# Stepper_Motor_Driver.net
KiCad netlist of a schematic drawn in Altium Designer
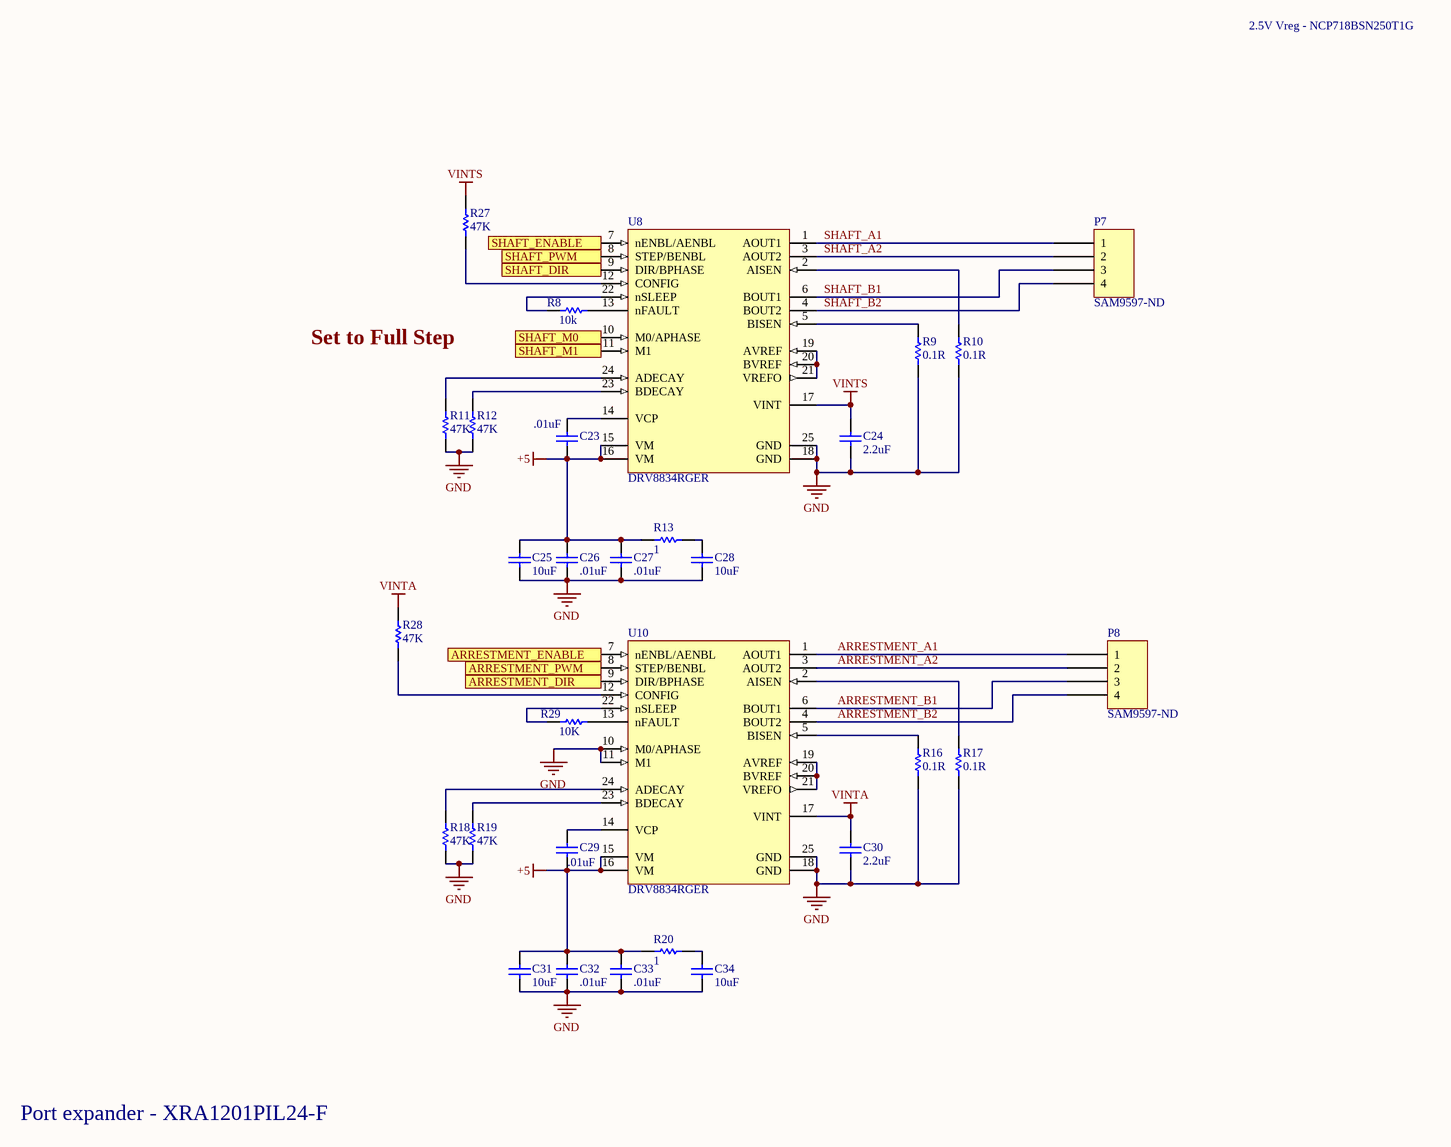
[diagram p0: Stepper Motor Driver.SchDoc]

(export (version "E")
  (design (tool "Eeschema 10.0.6"))
  (components
    (comp (ref "C23")
      (value ".01uF")
      (footprint "CAPC0402(1005)60_N")
      (description "CAP 220pF 25V ±10% 0402 (1005 Metric) Thickness 0.6mm SMD")
      (libsource (lib "Altium Content Vault") (part "CMP-1034-01365-1"))
    )
    (comp (ref "C24")
      (value "2.2uF")
      (footprint "CAPC0402(1005)60_N")
      (description "CAP 220pF 25V ±10% 0402 (1005 Metric) Thickness 0.6mm SMD")
      (libsource (lib "Altium Content Vault") (part "CMP-1034-01365-1"))
    )
    (comp (ref "C25")
      (value "10uF")
      (footprint "CAPC0402(1005)60_N")
      (description "CAP 220pF 25V ±10% 0402 (1005 Metric) Thickness 0.6mm SMD")
      (libsource (lib "Altium Content Vault") (part "CMP-1034-01365-1"))
    )
    (comp (ref "C26")
      (value ".01uF")
      (footprint "CAPC0402(1005)60_N")
      (description "CAP 220pF 25V ±10% 0402 (1005 Metric) Thickness 0.6mm SMD")
      (libsource (lib "Altium Content Vault") (part "CMP-1034-01365-1"))
    )
    (comp (ref "C27")
      (value ".01uF")
      (footprint "CAPC0402(1005)60_N")
      (description "CAP 220pF 25V ±10% 0402 (1005 Metric) Thickness 0.6mm SMD")
      (libsource (lib "Altium Content Vault") (part "CMP-1034-01365-1"))
    )
    (comp (ref "C28")
      (value "10uF")
      (footprint "CAPC0402(1005)60_N")
      (description "CAP 220pF 25V ±10% 0402 (1005 Metric) Thickness 0.6mm SMD")
      (libsource (lib "Altium Content Vault") (part "CMP-1034-01365-1"))
    )
    (comp (ref "C29")
      (value ".01uF")
      (footprint "CAPC0402(1005)60_N")
      (description "CAP 220pF 25V ±10% 0402 (1005 Metric) Thickness 0.6mm SMD")
      (libsource (lib "Altium Content Vault") (part "CMP-1034-01365-1"))
    )
    (comp (ref "C30")
      (value "2.2uF")
      (footprint "CAPC0402(1005)60_N")
      (description "CAP 220pF 25V ±10% 0402 (1005 Metric) Thickness 0.6mm SMD")
      (libsource (lib "Altium Content Vault") (part "CMP-1034-01365-1"))
    )
    (comp (ref "C31")
      (value "10uF")
      (footprint "CAPC0402(1005)60_N")
      (description "CAP 220pF 25V ±10% 0402 (1005 Metric) Thickness 0.6mm SMD")
      (libsource (lib "Altium Content Vault") (part "CMP-1034-01365-1"))
    )
    (comp (ref "C32")
      (value ".01uF")
      (footprint "CAPC0402(1005)60_N")
      (description "CAP 220pF 25V ±10% 0402 (1005 Metric) Thickness 0.6mm SMD")
      (libsource (lib "Altium Content Vault") (part "CMP-1034-01365-1"))
    )
    (comp (ref "C33")
      (value ".01uF")
      (footprint "CAPC0402(1005)60_N")
      (description "CAP 220pF 25V ±10% 0402 (1005 Metric) Thickness 0.6mm SMD")
      (libsource (lib "Altium Content Vault") (part "CMP-1034-01365-1"))
    )
    (comp (ref "C34")
      (value "10uF")
      (footprint "CAPC0402(1005)60_N")
      (description "CAP 220pF 25V ±10% 0402 (1005 Metric) Thickness 0.6mm SMD")
      (libsource (lib "Altium Content Vault") (part "CMP-1034-01365-1"))
    )
    (comp (ref "P7")
      (value "IPL1-104-01-L-S-RA-K")
      (footprint "IPL1-104-01-L-S-RA-K")
      (fields (field (name "SUPPLIER PART NUMBER 1") "SAM9597-ND"))
      (libsource (lib "ZLS_Schematic_lib") (part "IPL1-104-01-L-S-RA-K"))
    )
    (comp (ref "P8")
      (value "IPL1-104-01-L-S-RA-K")
      (footprint "IPL1-104-01-L-S-RA-K")
      (fields (field (name "SUPPLIER PART NUMBER 1") "SAM9597-ND"))
      (libsource (lib "ZLS_Schematic_lib") (part "IPL1-104-01-L-S-RA-K"))
    )
    (comp (ref "R8")
      (value "10k")
      (footprint "RESC0402(1005)_M")
      (libsource (lib "Altium Content Vault") (part "CMP-1011-00463-1"))
    )
    (comp (ref "R9")
      (value "0.1R")
      (footprint "RESC0402(1005)_M")
      (libsource (lib "Altium Content Vault") (part "CMP-1011-00463-1"))
    )
    (comp (ref "R10")
      (value "0.1R")
      (footprint "RESC0402(1005)_M")
      (libsource (lib "Altium Content Vault") (part "CMP-1011-00463-1"))
    )
    (comp (ref "R11")
      (value "47K")
      (footprint "RESC0402(1005)_M")
      (libsource (lib "Altium Content Vault") (part "CMP-1011-00463-1"))
    )
    (comp (ref "R12")
      (value "47K")
      (footprint "RESC0402(1005)_M")
      (libsource (lib "Altium Content Vault") (part "CMP-1011-00463-1"))
    )
    (comp (ref "R13")
      (value "1")
      (footprint "RESC0402(1005)_M")
      (libsource (lib "Altium Content Vault") (part "CMP-1011-00463-1"))
    )
    (comp (ref "R16")
      (value "0.1R")
      (footprint "RESC0402(1005)_M")
      (libsource (lib "Altium Content Vault") (part "CMP-1011-00463-1"))
    )
    (comp (ref "R17")
      (value "0.1R")
      (footprint "RESC0402(1005)_M")
      (libsource (lib "Altium Content Vault") (part "CMP-1011-00463-1"))
    )
    (comp (ref "R18")
      (value "47K")
      (footprint "RESC0402(1005)_M")
      (libsource (lib "Altium Content Vault") (part "CMP-1011-00463-1"))
    )
    (comp (ref "R19")
      (value "47K")
      (footprint "RESC0402(1005)_M")
      (libsource (lib "Altium Content Vault") (part "CMP-1011-00463-1"))
    )
    (comp (ref "R20")
      (value "1")
      (footprint "RESC0402(1005)_M")
      (libsource (lib "Altium Content Vault") (part "CMP-1011-00463-1"))
    )
    (comp (ref "R27")
      (value "47K")
      (footprint "RESC0402(1005)_M")
      (libsource (lib "Altium Content Vault") (part "CMP-1011-00463-1"))
    )
    (comp (ref "R28")
      (value "47K")
      (footprint "RESC0402(1005)_M")
      (libsource (lib "Altium Content Vault") (part "CMP-1011-00463-1"))
    )
    (comp (ref "R29")
      (value "10K")
      (footprint "RESC0402(1005)_M")
      (libsource (lib "Altium Content Vault") (part "CMP-1011-00463-1"))
    )
    (comp (ref "U8")
      (value "DRV8834RGER")
      (footprint "RGE0024B_V")
      (libsource (lib "Altium Content Vault") (part "TI-DRV8834RGE-24"))
    )
    (comp (ref "U10")
      (value "DRV8834RGER")
      (footprint "RGE0024B_V")
      (libsource (lib "Altium Content Vault") (part "TI-DRV8834RGE-24"))
    )
  )
  (nets
    (net (code "1") (name "+5") (class "Default")
      (node (ref "C23") (pin "1") (pinfunction "1_1") (pintype "passive"))
      (node (ref "C25") (pin "2") (pinfunction "2_2") (pintype "passive"))
      (node (ref "C26") (pin "2") (pinfunction "2_2") (pintype "passive"))
      (node (ref "C27") (pin "2") (pinfunction "2_2") (pintype "passive"))
      (node (ref "C29") (pin "1") (pinfunction "1_1") (pintype "passive"))
      (node (ref "C31") (pin "2") (pinfunction "2_2") (pintype "passive"))
      (node (ref "C32") (pin "2") (pinfunction "2_2") (pintype "passive"))
      (node (ref "C33") (pin "2") (pinfunction "2_2") (pintype "passive"))
      (node (ref "R13") (pin "1") (pinfunction "1_1") (pintype "passive"))
      (node (ref "R20") (pin "1") (pinfunction "1_1") (pintype "passive"))
      (node (ref "U10") (pin "15") (pinfunction "VM_15") (pintype "power_in"))
      (node (ref "U10") (pin "16") (pinfunction "VM_16") (pintype "power_in"))
      (node (ref "U8") (pin "15") (pinfunction "VM_15") (pintype "power_in"))
      (node (ref "U8") (pin "16") (pinfunction "VM_16") (pintype "power_in"))
    )
    (net (code "2") (name "/ARRESTMENT_A1") (class "Default")
      (node (ref "P8") (pin "1") (pinfunction "1_1") (pintype "passive"))
      (node (ref "U10") (pin "1") (pinfunction "AOUT1_1") (pintype "tri_state"))
    )
    (net (code "3") (name "/ARRESTMENT_A2") (class "Default")
      (node (ref "P8") (pin "2") (pinfunction "2_2") (pintype "passive"))
      (node (ref "U10") (pin "3") (pinfunction "AOUT2_3") (pintype "tri_state"))
    )
    (net (code "4") (name "/ARRESTMENT_B1") (class "Default")
      (node (ref "P8") (pin "3") (pinfunction "3_3") (pintype "passive"))
      (node (ref "U10") (pin "6") (pinfunction "BOUT1_6") (pintype "tri_state"))
    )
    (net (code "5") (name "/ARRESTMENT_B2") (class "Default")
      (node (ref "P8") (pin "4") (pinfunction "4_4") (pintype "passive"))
      (node (ref "U10") (pin "4") (pinfunction "BOUT2_4") (pintype "tri_state"))
    )
    (net (code "6") (name "/ARRESTMENT_DIR") (class "Default")
      (node (ref "U10") (pin "9") (pinfunction "DIR/BPHASE_9") (pintype "input"))
    )
    (net (code "7") (name "/ARRESTMENT_ENABLE") (class "Default")
      (node (ref "U10") (pin "7") (pinfunction "nENBL/AENBL_7") (pintype "input"))
    )
    (net (code "8") (name "/ARRESTMENT_PWM") (class "Default")
      (node (ref "U10") (pin "8") (pinfunction "STEP/BENBL_8") (pintype "input"))
    )
    (net (code "9") (name "/SHAFT_A1") (class "Default")
      (node (ref "P7") (pin "1") (pinfunction "1_1") (pintype "passive"))
      (node (ref "U8") (pin "1") (pinfunction "AOUT1_1") (pintype "tri_state"))
    )
    (net (code "10") (name "/SHAFT_A2") (class "Default")
      (node (ref "P7") (pin "2") (pinfunction "2_2") (pintype "passive"))
      (node (ref "U8") (pin "3") (pinfunction "AOUT2_3") (pintype "tri_state"))
    )
    (net (code "11") (name "/SHAFT_B1") (class "Default")
      (node (ref "P7") (pin "3") (pinfunction "3_3") (pintype "passive"))
      (node (ref "U8") (pin "6") (pinfunction "BOUT1_6") (pintype "tri_state"))
    )
    (net (code "12") (name "/SHAFT_B2") (class "Default")
      (node (ref "P7") (pin "4") (pinfunction "4_4") (pintype "passive"))
      (node (ref "U8") (pin "4") (pinfunction "BOUT2_4") (pintype "tri_state"))
    )
    (net (code "13") (name "/SHAFT_DIR") (class "Default")
      (node (ref "U8") (pin "9") (pinfunction "DIR/BPHASE_9") (pintype "input"))
    )
    (net (code "14") (name "/SHAFT_ENABLE") (class "Default")
      (node (ref "U8") (pin "7") (pinfunction "nENBL/AENBL_7") (pintype "input"))
    )
    (net (code "15") (name "/SHAFT_M0") (class "Default")
      (node (ref "U8") (pin "10") (pinfunction "M0/APHASE_10") (pintype "input"))
    )
    (net (code "16") (name "/SHAFT_M1") (class "Default")
      (node (ref "U8") (pin "11") (pinfunction "M1_11") (pintype "input"))
    )
    (net (code "17") (name "/SHAFT_PWM") (class "Default")
      (node (ref "U8") (pin "8") (pinfunction "STEP/BENBL_8") (pintype "input"))
    )
    (net (code "18") (name "GND") (class "Default")
      (node (ref "C24") (pin "1") (pinfunction "1_1") (pintype "passive"))
      (node (ref "C25") (pin "1") (pinfunction "1_1") (pintype "passive"))
      (node (ref "C26") (pin "1") (pinfunction "1_1") (pintype "passive"))
      (node (ref "C27") (pin "1") (pinfunction "1_1") (pintype "passive"))
      (node (ref "C28") (pin "1") (pinfunction "1_1") (pintype "passive"))
      (node (ref "C30") (pin "1") (pinfunction "1_1") (pintype "passive"))
      (node (ref "C31") (pin "1") (pinfunction "1_1") (pintype "passive"))
      (node (ref "C32") (pin "1") (pinfunction "1_1") (pintype "passive"))
      (node (ref "C33") (pin "1") (pinfunction "1_1") (pintype "passive"))
      (node (ref "C34") (pin "1") (pinfunction "1_1") (pintype "passive"))
      (node (ref "R10") (pin "2") (pinfunction "2_2") (pintype "passive"))
      (node (ref "R11") (pin "2") (pinfunction "2_2") (pintype "passive"))
      (node (ref "R12") (pin "2") (pinfunction "2_2") (pintype "passive"))
      (node (ref "R16") (pin "2") (pinfunction "2_2") (pintype "passive"))
      (node (ref "R17") (pin "2") (pinfunction "2_2") (pintype "passive"))
      (node (ref "R18") (pin "2") (pinfunction "2_2") (pintype "passive"))
      (node (ref "R19") (pin "2") (pinfunction "2_2") (pintype "passive"))
      (node (ref "R9") (pin "2") (pinfunction "2_2") (pintype "passive"))
      (node (ref "U10") (pin "10") (pinfunction "M0/APHASE_10") (pintype "input"))
      (node (ref "U10") (pin "11") (pinfunction "M1_11") (pintype "input"))
      (node (ref "U10") (pin "18") (pinfunction "GND_18") (pintype "power_in"))
      (node (ref "U10") (pin "25") (pinfunction "GND_25") (pintype "power_in"))
      (node (ref "U8") (pin "18") (pinfunction "GND_18") (pintype "power_in"))
      (node (ref "U8") (pin "25") (pinfunction "GND_25") (pintype "power_in"))
    )
    (net (code "19") (name "Net-(C28-Pad2)") (class "Default")
      (node (ref "C28") (pin "2") (pinfunction "2_2") (pintype "passive"))
      (node (ref "R13") (pin "2") (pinfunction "2_2") (pintype "passive"))
    )
    (net (code "20") (name "Net-(C34-Pad2)") (class "Default")
      (node (ref "C34") (pin "2") (pinfunction "2_2") (pintype "passive"))
      (node (ref "R20") (pin "2") (pinfunction "2_2") (pintype "passive"))
    )
    (net (code "21") (name "Net-(U8-ADECAY)") (class "Default")
      (node (ref "R11") (pin "1") (pinfunction "1_1") (pintype "passive"))
      (node (ref "U8") (pin "24") (pinfunction "ADECAY_24") (pintype "input"))
    )
    (net (code "22") (name "Net-(U8-AISEN)") (class "Default")
      (node (ref "R10") (pin "1") (pinfunction "1_1") (pintype "passive"))
      (node (ref "U8") (pin "2") (pinfunction "AISEN_2") (pintype "input"))
    )
    (net (code "23") (name "Net-(U8-AVREF)") (class "Default")
      (node (ref "U8") (pin "19") (pinfunction "AVREF_19") (pintype "input"))
      (node (ref "U8") (pin "20") (pinfunction "BVREF_20") (pintype "input"))
      (node (ref "U8") (pin "21") (pinfunction "VREFO_21") (pintype "output"))
    )
    (net (code "24") (name "Net-(U8-BDECAY)") (class "Default")
      (node (ref "R12") (pin "1") (pinfunction "1_1") (pintype "passive"))
      (node (ref "U8") (pin "23") (pinfunction "BDECAY_23") (pintype "input"))
    )
    (net (code "25") (name "Net-(U8-BISEN)") (class "Default")
      (node (ref "R9") (pin "1") (pinfunction "1_1") (pintype "passive"))
      (node (ref "U8") (pin "5") (pinfunction "BISEN_5") (pintype "input"))
    )
    (net (code "26") (name "Net-(U8-CONFIG)") (class "Default")
      (node (ref "R27") (pin "2") (pinfunction "2_2") (pintype "passive"))
      (node (ref "U8") (pin "12") (pinfunction "CONFIG_12") (pintype "input"))
    )
    (net (code "27") (name "Net-(U8-VCP)") (class "Default")
      (node (ref "C23") (pin "2") (pinfunction "2_2") (pintype "passive"))
      (node (ref "U8") (pin "14") (pinfunction "VCP_14") (pintype "passive"))
    )
    (net (code "28") (name "Net-(U8-nFAULT)") (class "Default")
      (node (ref "R8") (pin "2") (pinfunction "2_2") (pintype "passive"))
      (node (ref "U8") (pin "13") (pinfunction "nFAULT_13") (pintype "open_collector"))
    )
    (net (code "29") (name "Net-(U8-nSLEEP)") (class "Default")
      (node (ref "R8") (pin "1") (pinfunction "1_1") (pintype "passive"))
      (node (ref "U8") (pin "22") (pinfunction "nSLEEP_22") (pintype "input"))
    )
    (net (code "30") (name "Net-(U10-ADECAY)") (class "Default")
      (node (ref "R18") (pin "1") (pinfunction "1_1") (pintype "passive"))
      (node (ref "U10") (pin "24") (pinfunction "ADECAY_24") (pintype "input"))
    )
    (net (code "31") (name "Net-(U10-AISEN)") (class "Default")
      (node (ref "R17") (pin "1") (pinfunction "1_1") (pintype "passive"))
      (node (ref "U10") (pin "2") (pinfunction "AISEN_2") (pintype "input"))
    )
    (net (code "32") (name "Net-(U10-AVREF)") (class "Default")
      (node (ref "U10") (pin "19") (pinfunction "AVREF_19") (pintype "input"))
      (node (ref "U10") (pin "20") (pinfunction "BVREF_20") (pintype "input"))
      (node (ref "U10") (pin "21") (pinfunction "VREFO_21") (pintype "output"))
    )
    (net (code "33") (name "Net-(U10-BDECAY)") (class "Default")
      (node (ref "R19") (pin "1") (pinfunction "1_1") (pintype "passive"))
      (node (ref "U10") (pin "23") (pinfunction "BDECAY_23") (pintype "input"))
    )
    (net (code "34") (name "Net-(U10-BISEN)") (class "Default")
      (node (ref "R16") (pin "1") (pinfunction "1_1") (pintype "passive"))
      (node (ref "U10") (pin "5") (pinfunction "BISEN_5") (pintype "input"))
    )
    (net (code "35") (name "Net-(U10-CONFIG)") (class "Default")
      (node (ref "R28") (pin "2") (pinfunction "2_2") (pintype "passive"))
      (node (ref "U10") (pin "12") (pinfunction "CONFIG_12") (pintype "input"))
    )
    (net (code "36") (name "Net-(U10-VCP)") (class "Default")
      (node (ref "C29") (pin "2") (pinfunction "2_2") (pintype "passive"))
      (node (ref "U10") (pin "14") (pinfunction "VCP_14") (pintype "passive"))
    )
    (net (code "37") (name "Net-(U10-nFAULT)") (class "Default")
      (node (ref "R29") (pin "2") (pinfunction "2_2") (pintype "passive"))
      (node (ref "U10") (pin "13") (pinfunction "nFAULT_13") (pintype "open_collector"))
    )
    (net (code "38") (name "Net-(U10-nSLEEP)") (class "Default")
      (node (ref "R29") (pin "1") (pinfunction "1_1") (pintype "passive"))
      (node (ref "U10") (pin "22") (pinfunction "nSLEEP_22") (pintype "input"))
    )
    (net (code "39") (name "VINTA") (class "Default")
      (node (ref "C30") (pin "2") (pinfunction "2_2") (pintype "passive"))
      (node (ref "R28") (pin "1") (pinfunction "1_1") (pintype "passive"))
      (node (ref "U10") (pin "17") (pinfunction "VINT_17") (pintype "passive"))
    )
    (net (code "40") (name "VINTS") (class "Default")
      (node (ref "C24") (pin "2") (pinfunction "2_2") (pintype "passive"))
      (node (ref "R27") (pin "1") (pinfunction "1_1") (pintype "passive"))
      (node (ref "U8") (pin "17") (pinfunction "VINT_17") (pintype "passive"))
    )
  )
)
